# Opto_AQY280SX.net
KiCad netlist of a schematic drawn in Altium Designer
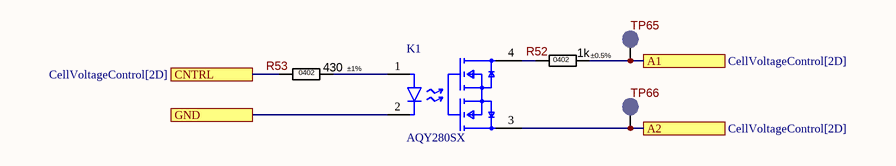
[diagram p0: Opto_AQY280SX.SchDoc]

(export (version "E")
  (design (tool "Eeschema 10.0.6"))
  (components
    (comp (ref "K1")
      (value "AQY280SX")
      (footprint "FP-AQY280SX-MFG")
      (description "AQY280SX AQY Photomos Series 120 mA 350 V 25 Ohm SMT 1 Channel Solid State Relay -SOP-4")
      (libsource (lib "EL.XXX.T01") (part "CMP-00287-00695349-1"))
    )
    (comp (ref "R52")
      (value "1k")
      (footprint "R_ANY_CHIP_0402_MED")
      (description "1 kOhms ±0.5% 1/16W 0402 Thick Film Resistor")
      (fields
        (field (name "TOLERANCE") "±0.5%")
        (field (name "PACKAGE") "0402")
        (field (name "PART NUMBER") "RC0402DR-071KL")
        (field (name "MANUFACTURER") "Yageo")
      )
      (libsource (lib "EL.XXX.T01") (part "RC0402DR-071KL"))
    )
    (comp (ref "R53")
      (value "430")
      (footprint "R_ANY_CHIP_0402_MED")
      (description "430 Ohms ±1% 1/16W 0402 Thick Film Resistor")
      (fields
        (field (name "TOLERANCE") "±1%")
        (field (name "PACKAGE") "0402")
        (field (name "PART NUMBER") "RC0402FR-07430RL")
        (field (name "MANUFACTURER") "Yageo")
      )
      (libsource (lib "EL.XXX.T01") (part "RC0402FR-07430RL"))
    )
    (comp (ref "TP65")
      (value "LED_LINK")
      (footprint "TP_SMD_2mm")
      (description "Test Point SMD Pad 1.0mm/1.5mm/2mm")
      (fields (field (name "PART NUMBER") "TP-PAD-SMD"))
      (libsource (lib "EL.XXX.T01") (part "TP-PAD-SMD"))
    )
    (comp (ref "TP66")
      (value "LED_LINK")
      (footprint "TP_SMD_2mm")
      (description "Test Point SMD Pad 1.0mm/1.5mm/2mm")
      (fields (field (name "PART NUMBER") "TP-PAD-SMD"))
      (libsource (lib "EL.XXX.T01") (part "TP-PAD-SMD"))
    )
  )
  (nets
    (net (code "1") (name "/A1") (class "Default")
      (node (ref "R52") (pin "2") (pintype "passive"))
      (node (ref "TP65") (pin "1") (pintype "passive"))
    )
    (net (code "2") (name "/A2") (class "Default")
      (node (ref "K1") (pin "3") (pinfunction "1_DRAIN_3") (pintype "passive"))
      (node (ref "TP66") (pin "1") (pintype "passive"))
    )
    (net (code "3") (name "/CNTRL") (class "Default") (node (ref "R53") (pin "1") (pintype "passive")))
    (net (code "4") (name "/GND") (class "Default")
      (node (ref "K1") (pin "2") (pinfunction "C_2") (pintype "passive"))
    )
    (net (code "5") (name "Net-(K1-2_DRAIN)") (class "Default")
      (node (ref "K1") (pin "4") (pinfunction "2_DRAIN_4") (pintype "passive"))
      (node (ref "R52") (pin "1") (pintype "passive"))
    )
    (net (code "6") (name "Net-(K1-A)") (class "Default")
      (node (ref "K1") (pin "1") (pinfunction "A_1") (pintype "passive"))
      (node (ref "R53") (pin "2") (pintype "passive"))
    )
  )
)
